# 10A_PWM_555.net
KiCad netlist of a schematic drawn in EasyEDA Pro
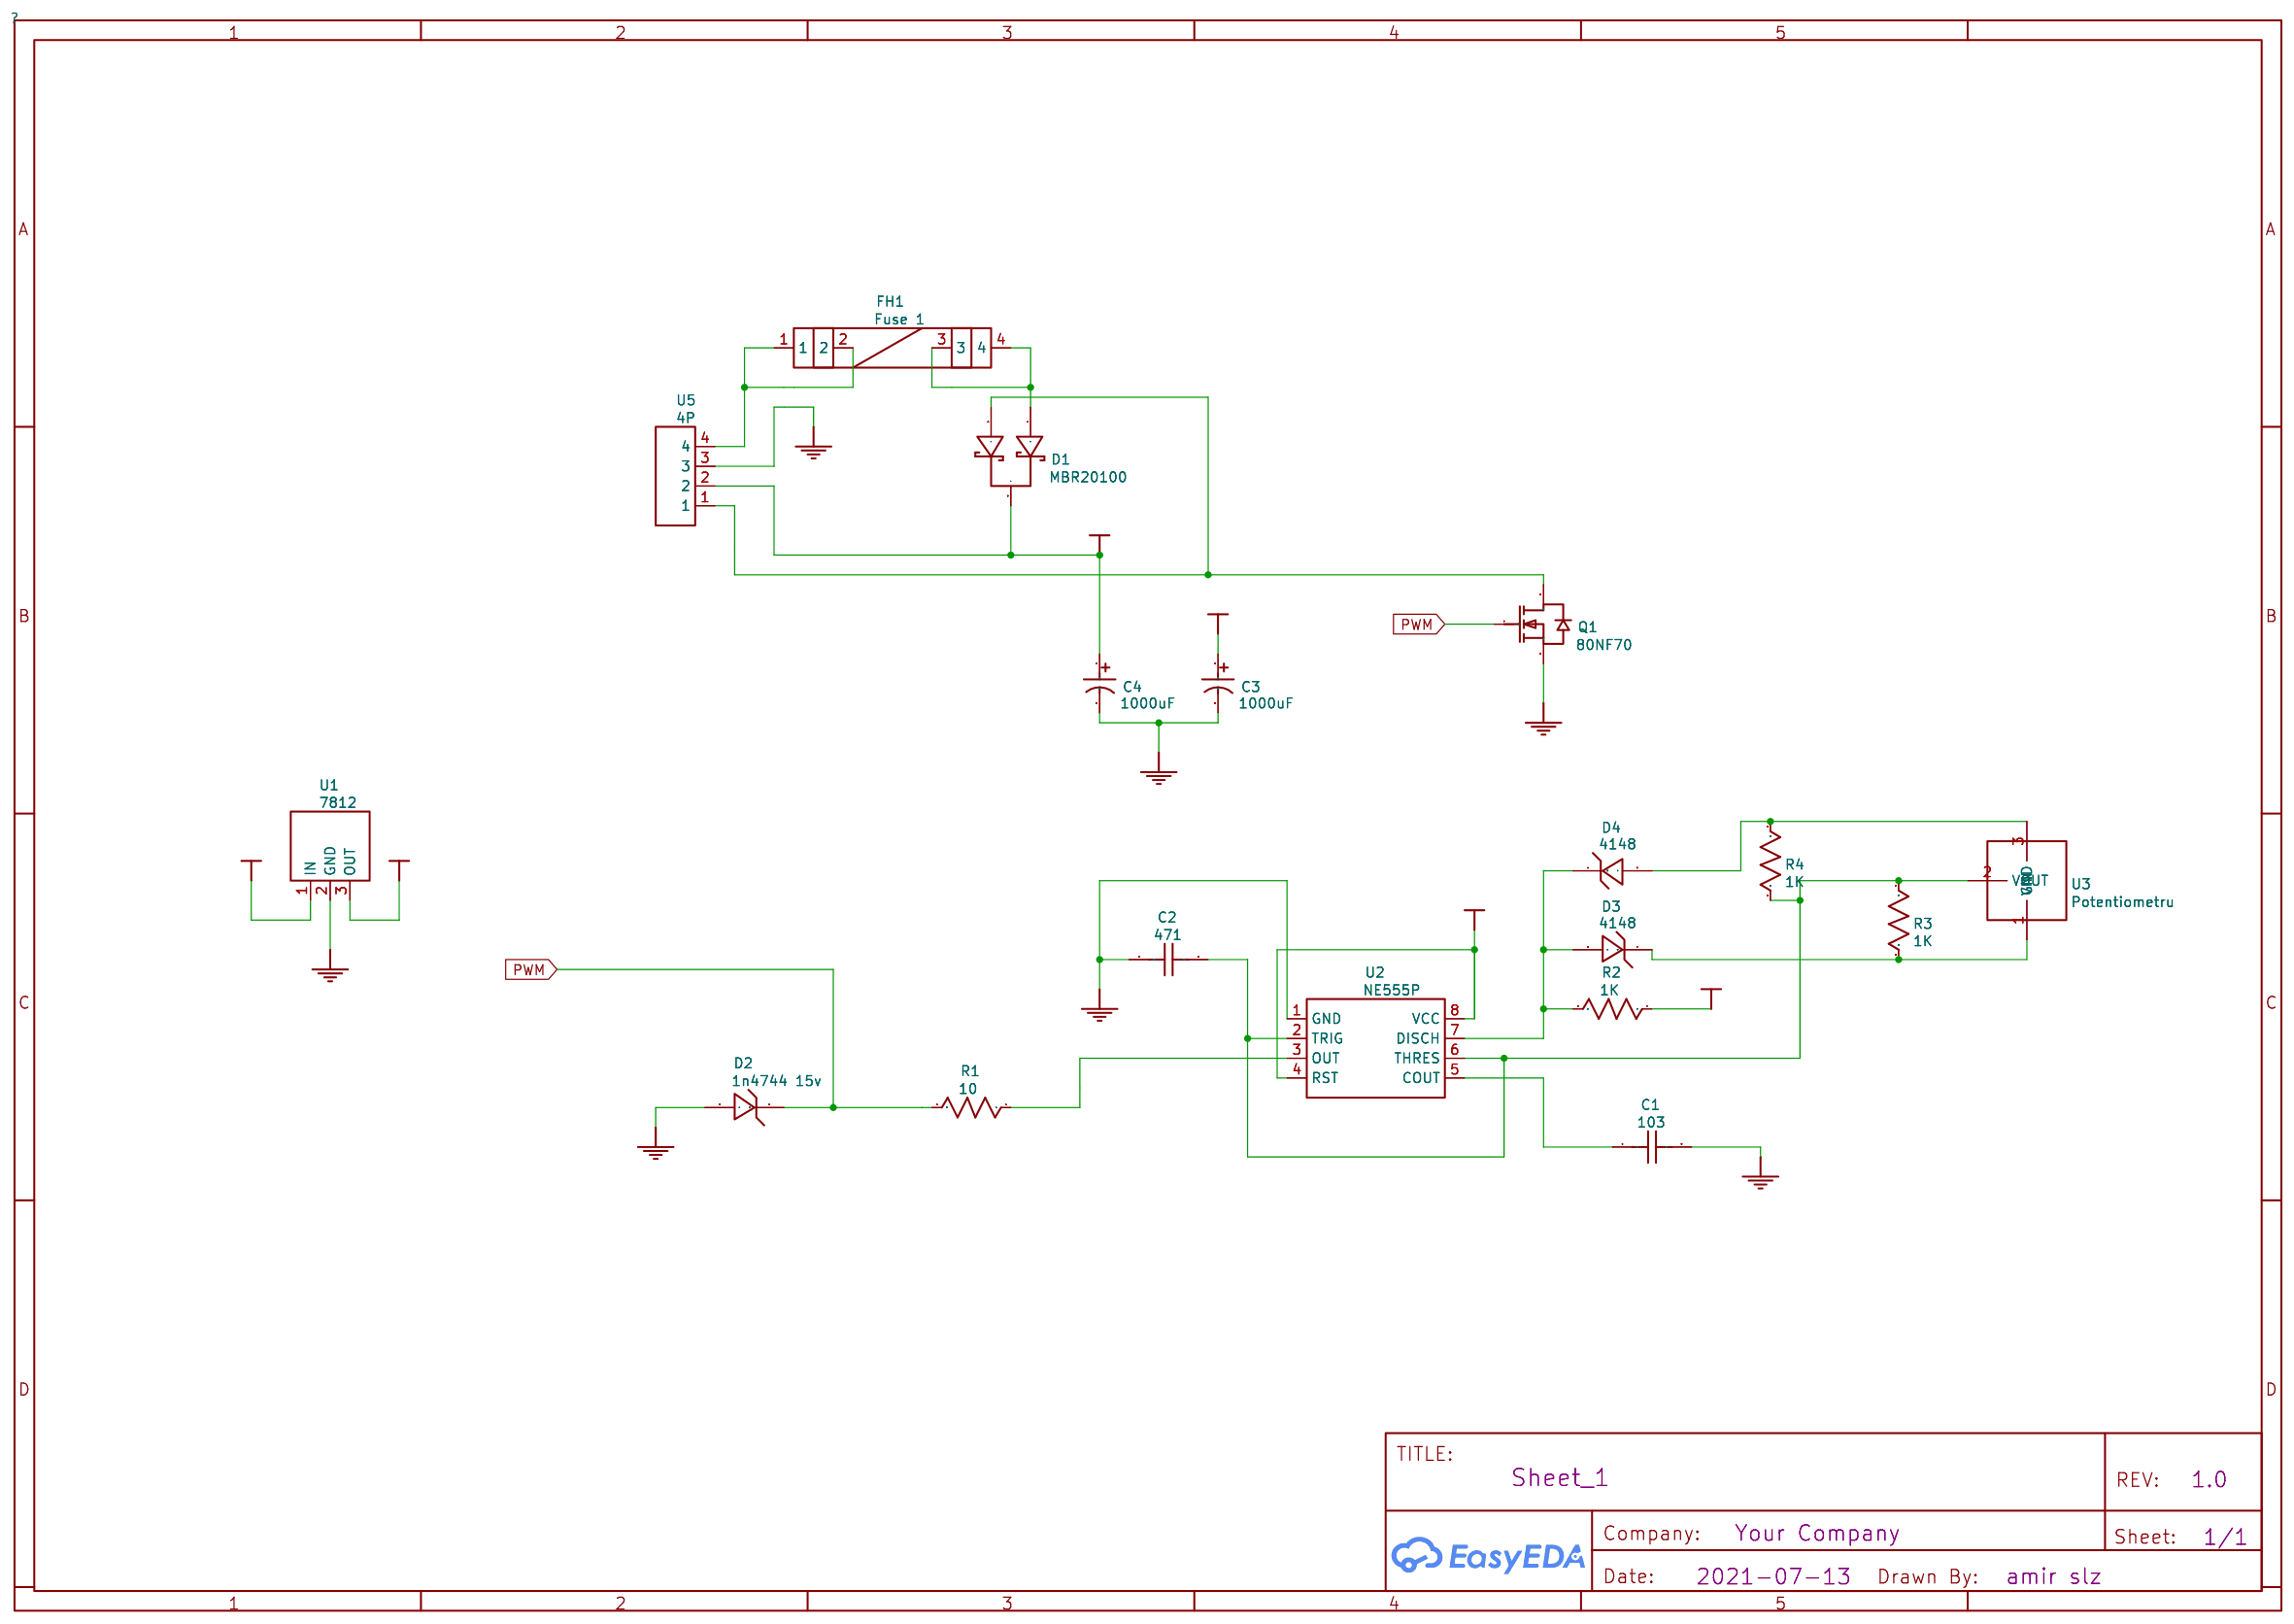
[diagram p0: schematic sheet]

(export (version "E")
  (design (tool "Eeschema 10.0.6"))
  (components
    (comp (ref "C1")
      (value "103")
      (fields
        (field (name "Manufacturer Part") "RDE5C1H100J0M1H03A")
        (field (name "Manufacturer") "muRata(村田)")
        (field (name "Contributor") "LCSC")
      )
      (libsource (lib "easyedapro") (part "103"))
    )
    (comp (ref "C2")
      (value "471")
      (fields
        (field (name "Manufacturer Part") "RDE5C1H100J0M1H03A")
        (field (name "Manufacturer") "muRata(村田)")
        (field (name "Contributor") "LCSC")
      )
      (libsource (lib "easyedapro") (part "471"))
    )
    (comp (ref "C3")
      (value "1000uF")
      (footprint "easyedapro:CAP-TH_BD12.5-P5.00-D0.6-FD")
      (fields (field (name "Manufacturer Part") "1000uF 50V") (field (name "Manufacturer") "ValuePro"))
      (libsource (lib "easyedapro") (part "1000uF"))
    )
    (comp (ref "C4")
      (value "1000uF")
      (footprint "easyedapro:CAP-TH_BD12.5-P5.00-D0.6-FD")
      (fields (field (name "Manufacturer Part") "1000uF 50V") (field (name "Manufacturer") "ValuePro"))
      (libsource (lib "easyedapro") (part "1000uF"))
    )
    (comp (ref "D1")
      (value "MBR20100")
      (footprint "easyedapro:TO-220AB-3_L10.4-W4.6-P2.54-L")
      (fields
        (field (name "Manufacturer Part") "MBR20150LCT")
        (field (name "Manufacturer") "Chongqing Pingwei Tech")
        (field (name "Contributor") "LCSC")
      )
      (libsource (lib "easyedapro") (part "MBR20100"))
    )
    (comp (ref "D2")
      (value "1n4744 15v")
      (footprint "easyedapro:DO-41_BD2.4-L4.7-P8.70-D0.9-RD")
      (fields
        (field (name "Manufacturer Part") "1N5919BRLG")
        (field (name "Manufacturer") "ON Semicon")
        (field (name "Contributor") "LCSC")
      )
      (libsource (lib "easyedapro") (part "1n4744 15v"))
    )
    (comp (ref "D3")
      (value "4148")
      (footprint "easyedapro:DO-41_BD2.4-L4.7-P8.70-D0.9-RD")
      (fields
        (field (name "Manufacturer Part") "1N5919BRLG")
        (field (name "Manufacturer") "ON Semicon")
        (field (name "Contributor") "LCSC")
      )
      (libsource (lib "easyedapro") (part "4148"))
    )
    (comp (ref "D4")
      (value "4148")
      (footprint "easyedapro:DO-41_BD2.4-L4.7-P8.70-D0.9-RD")
      (fields
        (field (name "Manufacturer Part") "1N5919BRLG")
        (field (name "Manufacturer") "ON Semicon")
        (field (name "Contributor") "LCSC")
      )
      (libsource (lib "easyedapro") (part "4148"))
    )
    (comp (ref "FH1")
      (value "Fuse 1")
      (fields
        (field (name "Manufacturer Part") "HF-004/J")
        (field (name "Manufacturer") "HOLLY(好利来)")
        (field (name "Contributor") "amir slz")
      )
      (libsource (lib "easyedapro") (part "Fuse 1"))
    )
    (comp (ref "Q1")
      (value "80NF70")
      (footprint "easyedapro:TO-220AB-3_L10.4-W4.6-P2.54-L")
      (fields
        (field (name "Manufacturer Part") "IRF540PBF")
        (field (name "Manufacturer") "VISHAY(威世)")
        (field (name "Contributor") "LCSC")
      )
      (libsource (lib "easyedapro") (part "80NF70"))
    )
    (comp (ref "R1")
      (value "10")
      (fields
        (field (name "Manufacturer Part") "0.4W 1% RESISTOR")
        (field (name "Contributor") "dannyjacket")
      )
      (libsource (lib "easyedapro") (part "10"))
    )
    (comp (ref "R2")
      (value "1K")
      (fields
        (field (name "Manufacturer Part") "0.4W 1% RESISTOR")
        (field (name "Contributor") "dannyjacket")
      )
      (libsource (lib "easyedapro") (part "1K"))
    )
    (comp (ref "R3")
      (value "1K")
      (fields
        (field (name "Manufacturer Part") "0.4W 1% RESISTOR")
        (field (name "Contributor") "dannyjacket")
      )
      (libsource (lib "easyedapro") (part "1K"))
    )
    (comp (ref "R4")
      (value "1K")
      (fields
        (field (name "Manufacturer Part") "0.4W 1% RESISTOR")
        (field (name "Contributor") "dannyjacket")
      )
      (libsource (lib "") (part "1K_1"))
    )
    (comp (ref "U1")
      (value "7812")
      (footprint "easyedapro:TO-220-3_L10.0-W4.5-P2.54-L")
      (fields (field (name "Manufacturer") "Foshan Blue Rocket Elec") (field (name "Contributor") "LCSC"))
      (libsource (lib "easyedapro") (part "7812"))
    )
    (comp (ref "U2")
      (value "NE555P")
      (footprint "easyedapro:DIP-8_L9.8-W6.6-P2.54-LS7.6-BL")
      (fields (field (name "Manufacturer") "TI"))
      (libsource (lib "easyedapro") (part "NE555P"))
    )
    (comp (ref "U3")
      (value "Potentiometru")
      (fields (field (name "Contributor") "DMCalin"))
      (libsource (lib "easyedapro") (part "Potentiometru"))
    )
    (comp (ref "U5")
      (value "4P")
      (fields
        (field (name "Manufacturer Part") "DBT50B-9.5-4P")
        (field (name "Manufacturer") "DIBO")
        (field (name "Contributor") "LCSC")
      )
      (libsource (lib "easyedapro") (part "4P"))
    )
  )
  (nets
    (net (code "1") (name "+12V") (class "Default")
      (node (ref "C3") (pin "1") (pinfunction "1_1") (pintype "input"))
      (node (ref "R2") (pin "1") (pinfunction "1_1") (pintype "unspecified"))
      (node (ref "U1") (pin "3") (pinfunction "OUT_3") (pintype "unspecified"))
      (node (ref "U2") (pin "4") (pinfunction "RST_4") (pintype "unspecified"))
      (node (ref "U2") (pin "8") (pinfunction "VCC_8") (pintype "unspecified"))
    )
    (net (code "2") (name "GND") (class "Default")
      (node (ref "C1") (pin "2") (pinfunction "2_2") (pintype "unspecified"))
      (node (ref "C2") (pin "1") (pinfunction "1_1") (pintype "unspecified"))
      (node (ref "C3") (pin "2") (pinfunction "2_2") (pintype "input"))
      (node (ref "C4") (pin "2") (pinfunction "2_2") (pintype "input"))
      (node (ref "D2") (pin "2") (pinfunction "A_2") (pintype "unspecified"))
      (node (ref "Q1") (pin "3") (pinfunction "S_3") (pintype "unspecified"))
      (node (ref "U1") (pin "2") (pinfunction "GND_2") (pintype "unspecified"))
      (node (ref "U2") (pin "1") (pinfunction "GND_1") (pintype "unspecified"))
      (node (ref "U5") (pin "3") (pinfunction "3_3") (pintype "unspecified"))
    )
    (net (code "3") (name "Net-(D1-+-Pad1)") (class "Default")
      (node (ref "D1") (pin "1") (pinfunction "+_1") (pintype "unspecified"))
      (node (ref "FH1") (pin "3") (pinfunction "3_3") (pintype "unspecified"))
      (node (ref "FH1") (pin "4") (pinfunction "4_4") (pintype "unspecified"))
    )
    (net (code "4") (name "Net-(D3-A)") (class "Default")
      (node (ref "D3") (pin "2") (pinfunction "A_2") (pintype "unspecified"))
      (node (ref "D4") (pin "1") (pinfunction "C_1") (pintype "unspecified"))
      (node (ref "R2") (pin "2") (pinfunction "2_2") (pintype "unspecified"))
      (node (ref "U2") (pin "7") (pinfunction "DISCH_7") (pintype "unspecified"))
    )
    (net (code "5") (name "Net-(D3-C)") (class "Default")
      (node (ref "D3") (pin "1") (pinfunction "C_1") (pintype "unspecified"))
      (node (ref "R3") (pin "2") (pinfunction "2_2") (pintype "unspecified"))
      (node (ref "U3") (pin "1") (pinfunction "VIN_1") (pintype "unspecified"))
    )
    (net (code "6") (name "Net-(D4-A)") (class "Default")
      (node (ref "D4") (pin "2") (pinfunction "A_2") (pintype "unspecified"))
      (node (ref "R4") (pin "2") (pinfunction "2_2") (pintype "unspecified"))
      (node (ref "U3") (pin "3") (pinfunction "GND_3") (pintype "unspecified"))
    )
    (net (code "7") (name "Net-(FH1-Pad1)") (class "Default")
      (node (ref "FH1") (pin "1") (pinfunction "1_1") (pintype "unspecified"))
      (node (ref "FH1") (pin "2") (pinfunction "2_2") (pintype "unspecified"))
      (node (ref "U5") (pin "4") (pinfunction "4_4") (pintype "unspecified"))
    )
    (net (code "8") (name "Net-(Q1-D)") (class "Default")
      (node (ref "D1") (pin "3") (pinfunction "+_3") (pintype "unspecified"))
      (node (ref "Q1") (pin "2") (pinfunction "D_2") (pintype "unspecified"))
      (node (ref "U5") (pin "1") (pinfunction "1_1") (pintype "unspecified"))
    )
    (net (code "9") (name "Net-(U2-COUT)") (class "Default")
      (node (ref "C1") (pin "1") (pinfunction "1_1") (pintype "unspecified"))
      (node (ref "U2") (pin "5") (pinfunction "COUT_5") (pintype "unspecified"))
    )
    (net (code "10") (name "Net-(U2-OUT)") (class "Default")
      (node (ref "R1") (pin "1") (pinfunction "1_1") (pintype "unspecified"))
      (node (ref "U2") (pin "3") (pinfunction "OUT_3") (pintype "unspecified"))
    )
    (net (code "11") (name "Net-(U2-THRES)") (class "Default")
      (node (ref "C2") (pin "2") (pinfunction "2_2") (pintype "unspecified"))
      (node (ref "R3") (pin "1") (pinfunction "1_1") (pintype "unspecified"))
      (node (ref "R4") (pin "1") (pinfunction "1_1") (pintype "unspecified"))
      (node (ref "U2") (pin "2") (pinfunction "TRIG_2") (pintype "unspecified"))
      (node (ref "U2") (pin "6") (pinfunction "THRES_6") (pintype "unspecified"))
      (node (ref "U3") (pin "2") (pinfunction "VOUT_2") (pintype "unspecified"))
    )
    (net (code "12") (name "PWM") (class "Default")
      (node (ref "D2") (pin "1") (pinfunction "C_1") (pintype "unspecified"))
      (node (ref "Q1") (pin "1") (pinfunction "G_1") (pintype "unspecified"))
      (node (ref "R1") (pin "2") (pinfunction "2_2") (pintype "unspecified"))
    )
    (net (code "13") (name "VCC") (class "Default")
      (node (ref "C4") (pin "1") (pinfunction "1_1") (pintype "input"))
      (node (ref "D1") (pin "2") (pinfunction "-_2") (pintype "unspecified"))
      (node (ref "U1") (pin "1") (pinfunction "IN_1") (pintype "unspecified"))
      (node (ref "U5") (pin "2") (pinfunction "2_2") (pintype "unspecified"))
    )
  )
)
